# two_digits_pcb.net
KiCad netlist of a schematic drawn in EAGLE
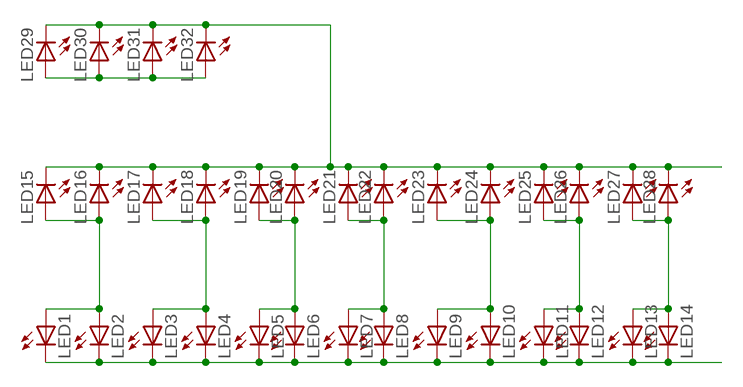
[diagram p0: schematic, sheet 1]

(export (version "E")
  (design (tool "Eeschema 10.0.6"))
  (components
    (comp (ref "LED1")
      (value "LED5MM")
      (footprint "eagle-import:LED5MM")
      (libsource (lib "eagle-import") (part "LED5MM"))
    )
    (comp (ref "LED2")
      (value "LED5MM")
      (footprint "eagle-import:LED5MM")
      (libsource (lib "eagle-import") (part "LED5MM"))
    )
    (comp (ref "LED3")
      (value "LED5MM")
      (footprint "eagle-import:LED5MM")
      (libsource (lib "eagle-import") (part "LED5MM"))
    )
    (comp (ref "LED4")
      (value "LED5MM")
      (footprint "eagle-import:LED5MM")
      (libsource (lib "eagle-import") (part "LED5MM"))
    )
    (comp (ref "LED5")
      (value "LED5MM")
      (footprint "eagle-import:LED5MM")
      (libsource (lib "eagle-import") (part "LED5MM"))
    )
    (comp (ref "LED6")
      (value "LED5MM")
      (footprint "eagle-import:LED5MM")
      (libsource (lib "eagle-import") (part "LED5MM"))
    )
    (comp (ref "LED7")
      (value "LED5MM")
      (footprint "eagle-import:LED5MM")
      (libsource (lib "eagle-import") (part "LED5MM"))
    )
    (comp (ref "LED8")
      (value "LED5MM")
      (footprint "eagle-import:LED5MM")
      (libsource (lib "eagle-import") (part "LED5MM"))
    )
    (comp (ref "LED9")
      (value "LED5MM")
      (footprint "eagle-import:LED5MM")
      (libsource (lib "eagle-import") (part "LED5MM"))
    )
    (comp (ref "LED10")
      (value "LED5MM")
      (footprint "eagle-import:LED5MM")
      (libsource (lib "eagle-import") (part "LED5MM"))
    )
    (comp (ref "LED11")
      (value "LED5MM")
      (footprint "eagle-import:LED5MM")
      (libsource (lib "eagle-import") (part "LED5MM"))
    )
    (comp (ref "LED12")
      (value "LED5MM")
      (footprint "eagle-import:LED5MM")
      (libsource (lib "eagle-import") (part "LED5MM"))
    )
    (comp (ref "LED13")
      (value "LED5MM")
      (footprint "eagle-import:LED5MM")
      (libsource (lib "eagle-import") (part "LED5MM"))
    )
    (comp (ref "LED14")
      (value "LED5MM")
      (footprint "eagle-import:LED5MM")
      (libsource (lib "eagle-import") (part "LED5MM"))
    )
    (comp (ref "LED15")
      (value "LED5MM")
      (footprint "eagle-import:LED5MM")
      (libsource (lib "eagle-import") (part "LED5MM"))
    )
    (comp (ref "LED16")
      (value "LED5MM")
      (footprint "eagle-import:LED5MM")
      (libsource (lib "eagle-import") (part "LED5MM"))
    )
    (comp (ref "LED17")
      (value "LED5MM")
      (footprint "eagle-import:LED5MM")
      (libsource (lib "eagle-import") (part "LED5MM"))
    )
    (comp (ref "LED18")
      (value "LED5MM")
      (footprint "eagle-import:LED5MM")
      (libsource (lib "eagle-import") (part "LED5MM"))
    )
    (comp (ref "LED19")
      (value "LED5MM")
      (footprint "eagle-import:LED5MM")
      (libsource (lib "eagle-import") (part "LED5MM"))
    )
    (comp (ref "LED20")
      (value "LED5MM")
      (footprint "eagle-import:LED5MM")
      (libsource (lib "eagle-import") (part "LED5MM"))
    )
    (comp (ref "LED21")
      (value "LED5MM")
      (footprint "eagle-import:LED5MM")
      (libsource (lib "eagle-import") (part "LED5MM"))
    )
    (comp (ref "LED22")
      (value "LED5MM")
      (footprint "eagle-import:LED5MM")
      (libsource (lib "eagle-import") (part "LED5MM"))
    )
    (comp (ref "LED23")
      (value "LED5MM")
      (footprint "eagle-import:LED5MM")
      (libsource (lib "eagle-import") (part "LED5MM"))
    )
    (comp (ref "LED24")
      (value "LED5MM")
      (footprint "eagle-import:LED5MM")
      (libsource (lib "eagle-import") (part "LED5MM"))
    )
    (comp (ref "LED25")
      (value "LED5MM")
      (footprint "eagle-import:LED5MM")
      (libsource (lib "eagle-import") (part "LED5MM"))
    )
    (comp (ref "LED26")
      (value "LED5MM")
      (footprint "eagle-import:LED5MM")
      (libsource (lib "eagle-import") (part "LED5MM"))
    )
    (comp (ref "LED27")
      (value "LED5MM")
      (footprint "eagle-import:LED5MM")
      (libsource (lib "eagle-import") (part "LED5MM"))
    )
    (comp (ref "LED28")
      (value "LED5MM")
      (footprint "eagle-import:LED5MM")
      (libsource (lib "eagle-import") (part "LED5MM"))
    )
    (comp (ref "LED29")
      (value "LED5MM")
      (footprint "eagle-import:LED5MM")
      (libsource (lib "eagle-import") (part "LED5MM"))
    )
    (comp (ref "LED30")
      (value "LED5MM")
      (footprint "eagle-import:LED5MM")
      (libsource (lib "eagle-import") (part "LED5MM"))
    )
    (comp (ref "LED31")
      (value "LED5MM")
      (footprint "eagle-import:LED5MM")
      (libsource (lib "eagle-import") (part "LED5MM"))
    )
    (comp (ref "LED32")
      (value "LED5MM")
      (footprint "eagle-import:LED5MM")
      (libsource (lib "eagle-import") (part "LED5MM"))
    )
  )
  (nets
    (net (code "1") (name "Net-(LED1-C)") (class "Default")
      (node (ref "LED1") (pin "K") (pinfunction "C_K") (pintype "passive"))
      (node (ref "LED10") (pin "K") (pinfunction "C_K") (pintype "passive"))
      (node (ref "LED11") (pin "K") (pinfunction "C_K") (pintype "passive"))
      (node (ref "LED12") (pin "K") (pinfunction "C_K") (pintype "passive"))
      (node (ref "LED13") (pin "K") (pinfunction "C_K") (pintype "passive"))
      (node (ref "LED14") (pin "K") (pinfunction "C_K") (pintype "passive"))
      (node (ref "LED2") (pin "K") (pinfunction "C_K") (pintype "passive"))
      (node (ref "LED3") (pin "K") (pinfunction "C_K") (pintype "passive"))
      (node (ref "LED4") (pin "K") (pinfunction "C_K") (pintype "passive"))
      (node (ref "LED5") (pin "K") (pinfunction "C_K") (pintype "passive"))
      (node (ref "LED6") (pin "K") (pinfunction "C_K") (pintype "passive"))
      (node (ref "LED7") (pin "K") (pinfunction "C_K") (pintype "passive"))
      (node (ref "LED8") (pin "K") (pinfunction "C_K") (pintype "passive"))
      (node (ref "LED9") (pin "K") (pinfunction "C_K") (pintype "passive"))
    )
    (net (code "2") (name "Net-(LED1-PadA)") (class "Default")
      (node (ref "LED1") (pin "A") (pinfunction "A_A") (pintype "passive"))
      (node (ref "LED15") (pin "A") (pinfunction "A_A") (pintype "passive"))
      (node (ref "LED16") (pin "A") (pinfunction "A_A") (pintype "passive"))
      (node (ref "LED2") (pin "A") (pinfunction "A_A") (pintype "passive"))
    )
    (net (code "3") (name "Net-(LED10-PadA)") (class "Default")
      (node (ref "LED10") (pin "A") (pinfunction "A_A") (pintype "passive"))
      (node (ref "LED23") (pin "A") (pinfunction "A_A") (pintype "passive"))
      (node (ref "LED24") (pin "A") (pinfunction "A_A") (pintype "passive"))
      (node (ref "LED9") (pin "A") (pinfunction "A_A") (pintype "passive"))
    )
    (net (code "4") (name "Net-(LED11-PadA)") (class "Default")
      (node (ref "LED11") (pin "A") (pinfunction "A_A") (pintype "passive"))
      (node (ref "LED12") (pin "A") (pinfunction "A_A") (pintype "passive"))
      (node (ref "LED25") (pin "A") (pinfunction "A_A") (pintype "passive"))
      (node (ref "LED26") (pin "A") (pinfunction "A_A") (pintype "passive"))
    )
    (net (code "5") (name "Net-(LED13-PadA)") (class "Default")
      (node (ref "LED13") (pin "A") (pinfunction "A_A") (pintype "passive"))
      (node (ref "LED14") (pin "A") (pinfunction "A_A") (pintype "passive"))
      (node (ref "LED27") (pin "A") (pinfunction "A_A") (pintype "passive"))
      (node (ref "LED28") (pin "A") (pinfunction "A_A") (pintype "passive"))
    )
    (net (code "6") (name "Net-(LED15-C)") (class "Default")
      (node (ref "LED15") (pin "K") (pinfunction "C_K") (pintype "passive"))
      (node (ref "LED16") (pin "K") (pinfunction "C_K") (pintype "passive"))
      (node (ref "LED17") (pin "K") (pinfunction "C_K") (pintype "passive"))
      (node (ref "LED18") (pin "K") (pinfunction "C_K") (pintype "passive"))
      (node (ref "LED19") (pin "K") (pinfunction "C_K") (pintype "passive"))
      (node (ref "LED20") (pin "K") (pinfunction "C_K") (pintype "passive"))
      (node (ref "LED21") (pin "K") (pinfunction "C_K") (pintype "passive"))
      (node (ref "LED22") (pin "K") (pinfunction "C_K") (pintype "passive"))
      (node (ref "LED23") (pin "K") (pinfunction "C_K") (pintype "passive"))
      (node (ref "LED24") (pin "K") (pinfunction "C_K") (pintype "passive"))
      (node (ref "LED25") (pin "K") (pinfunction "C_K") (pintype "passive"))
      (node (ref "LED26") (pin "K") (pinfunction "C_K") (pintype "passive"))
      (node (ref "LED27") (pin "K") (pinfunction "C_K") (pintype "passive"))
      (node (ref "LED28") (pin "K") (pinfunction "C_K") (pintype "passive"))
      (node (ref "LED29") (pin "K") (pinfunction "C_K") (pintype "passive"))
      (node (ref "LED30") (pin "K") (pinfunction "C_K") (pintype "passive"))
      (node (ref "LED31") (pin "K") (pinfunction "C_K") (pintype "passive"))
      (node (ref "LED32") (pin "K") (pinfunction "C_K") (pintype "passive"))
    )
    (net (code "7") (name "Net-(LED17-PadA)") (class "Default")
      (node (ref "LED17") (pin "A") (pinfunction "A_A") (pintype "passive"))
      (node (ref "LED18") (pin "A") (pinfunction "A_A") (pintype "passive"))
      (node (ref "LED3") (pin "A") (pinfunction "A_A") (pintype "passive"))
      (node (ref "LED4") (pin "A") (pinfunction "A_A") (pintype "passive"))
    )
    (net (code "8") (name "Net-(LED19-PadA)") (class "Default")
      (node (ref "LED19") (pin "A") (pinfunction "A_A") (pintype "passive"))
      (node (ref "LED20") (pin "A") (pinfunction "A_A") (pintype "passive"))
      (node (ref "LED5") (pin "A") (pinfunction "A_A") (pintype "passive"))
      (node (ref "LED6") (pin "A") (pinfunction "A_A") (pintype "passive"))
    )
    (net (code "9") (name "Net-(LED21-PadA)") (class "Default")
      (node (ref "LED21") (pin "A") (pinfunction "A_A") (pintype "passive"))
      (node (ref "LED22") (pin "A") (pinfunction "A_A") (pintype "passive"))
      (node (ref "LED7") (pin "A") (pinfunction "A_A") (pintype "passive"))
      (node (ref "LED8") (pin "A") (pinfunction "A_A") (pintype "passive"))
    )
    (net (code "10") (name "Net-(LED29-PadA)") (class "Default")
      (node (ref "LED29") (pin "A") (pinfunction "A_A") (pintype "passive"))
      (node (ref "LED30") (pin "A") (pinfunction "A_A") (pintype "passive"))
      (node (ref "LED31") (pin "A") (pinfunction "A_A") (pintype "passive"))
      (node (ref "LED32") (pin "A") (pinfunction "A_A") (pintype "passive"))
    )
  )
)
